# SkyKontrol-Display.net
KiCad netlist of a schematic drawn in EAGLE
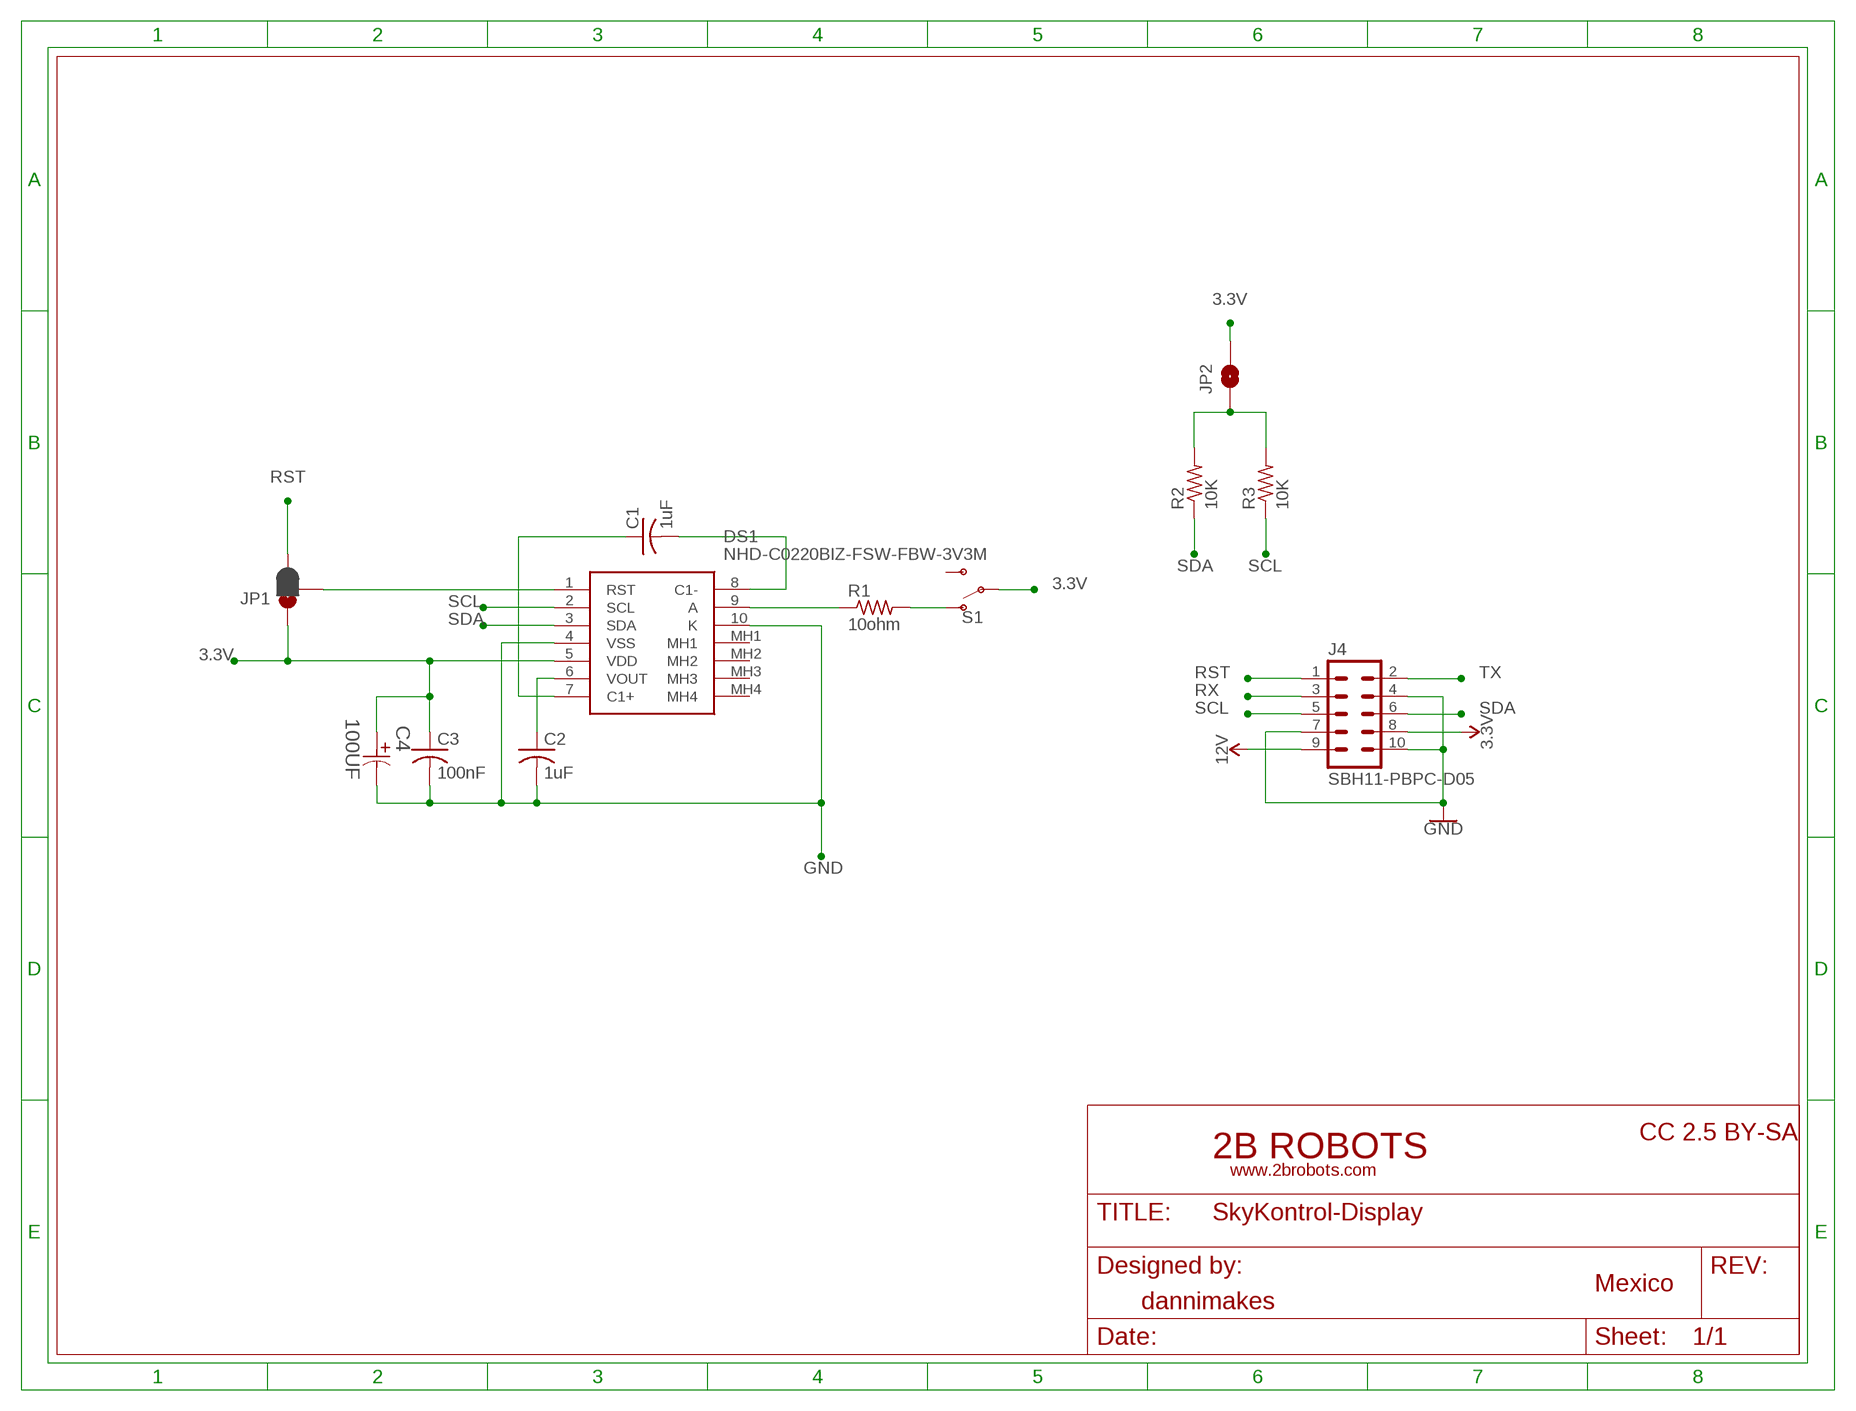
[diagram p0: schematic, sheet 1]

(export (version "E")
  (design (tool "Eeschema 10.0.6"))
  (components
    (comp (ref "C1")
      (value "1uF")
      (footprint "eagle-import:C0603K")
      (libsource (lib "eagle-import") (part "C-USC0603K"))
    )
    (comp (ref "C2")
      (value "1uF")
      (footprint "eagle-import:C0603K")
      (libsource (lib "eagle-import") (part "C-USC0603K"))
    )
    (comp (ref "C3")
      (value "100nF")
      (footprint "eagle-import:C0603K")
      (libsource (lib "eagle-import") (part "C-USC0603K"))
    )
    (comp (ref "C4")
      (value "100UF")
      (footprint "eagle-import:CAPAE660X800N")
      (fields (field (name "MPN") "EEE-HA1E101XP") (field (name "TOLERANCE") "±20 %"))
      (libsource (lib "eagle-import") (part "EEE--CASE-D8HA1E101XP"))
    )
    (comp (ref "DS1")
      (value "NHD-C0220BIZ-FSW-FBW-3V3M")
      (footprint "eagle-import:NHDC0220BIZFSWFBW3V3M")
      (fields (field (name "MOUSER_PART_NUMBER") "763-C0220BIZ-FSW-FBW"))
      (libsource (lib "eagle-import") (part "NHD-C0220BIZ-FSW-FBW-3V3M"))
    )
    (comp (ref "J4")
      (value "SBH11-PBPC-D05")
      (footprint "eagle-import:SBH11-PBPC-D05")
      (libsource (lib "eagle-import") (part "SBH11-PBPC-D05"))
    )
    (comp (ref "JP1")
      (value "JUMPER-SMT_3_1-NC_PASTE_SILK")
      (footprint "eagle-import:SMT-JUMPER_3_1-NC_PASTE_SILK")
      (libsource (lib "eagle-import") (part "JUMPER-SMT_3_1-NC_PASTE_SILK"))
    )
    (comp (ref "JP2")
      (value "JUMPER-SMT_2_NO_SILK")
      (footprint "eagle-import:SMT-JUMPER_2_NO_SILK")
      (libsource (lib "eagle-import") (part "JUMPER-SMT_2_NO_SILK"))
    )
    (comp (ref "R1")
      (value "10ohm")
      (footprint "eagle-import:R0805")
      (libsource (lib "eagle-import") (part "R-US_R0805"))
    )
    (comp (ref "R2")
      (value "10K")
      (footprint "eagle-import:R0805")
      (libsource (lib "eagle-import") (part "R-US_R0805"))
    )
    (comp (ref "R3")
      (value "10K")
      (footprint "eagle-import:R0805")
      (libsource (lib "eagle-import") (part "R-US_R0805"))
    )
    (comp (ref "S1")
      (value "SWITCH-SPDT-SMD-RIGHT-ANGLE")
      (footprint "eagle-import:SWITCH_SPST_SMD_A")
      (libsource (lib "eagle-import") (part "SWITCH-SPDT-SMD-RIGHT-ANGLE"))
    )
  )
  (nets
    (net (code "1") (name "/RST") (class "Default")
      (node (ref "J4") (pin "1") (pinfunction "1_1") (pintype "passive"))
      (node (ref "JP1") (pin "3") (pinfunction "3_3") (pintype "passive"))
    )
    (net (code "2") (name "/RX") (class "Default")
      (node (ref "J4") (pin "3") (pinfunction "3_3") (pintype "passive"))
    )
    (net (code "3") (name "/SCL") (class "Default")
      (node (ref "DS1") (pin "2") (pinfunction "SCL_2") (pintype "bidirectional"))
      (node (ref "J4") (pin "5") (pinfunction "5_5") (pintype "passive"))
      (node (ref "R3") (pin "1") (pinfunction "1_1") (pintype "passive"))
    )
    (net (code "4") (name "/SDA") (class "Default")
      (node (ref "DS1") (pin "3") (pinfunction "SDA_3") (pintype "bidirectional"))
      (node (ref "J4") (pin "6") (pinfunction "6_6") (pintype "passive"))
      (node (ref "R2") (pin "1") (pinfunction "1_1") (pintype "passive"))
    )
    (net (code "5") (name "/TX") (class "Default")
      (node (ref "J4") (pin "2") (pinfunction "2_2") (pintype "passive"))
    )
    (net (code "6") (name "3.3V") (class "Default")
      (node (ref "C3") (pin "1") (pinfunction "1_1") (pintype "passive"))
      (node (ref "C4") (pin "1") (pinfunction "1_1") (pintype "passive"))
      (node (ref "DS1") (pin "5") (pinfunction "VDD_5") (pintype "bidirectional"))
      (node (ref "J4") (pin "8") (pinfunction "8_8") (pintype "passive"))
      (node (ref "JP1") (pin "1") (pinfunction "1_1") (pintype "passive"))
      (node (ref "JP2") (pin "2") (pinfunction "2_2") (pintype "passive"))
      (node (ref "S1") (pin "2") (pinfunction "P_2") (pintype "passive"))
    )
    (net (code "7") (name "12V") (class "Default")
      (node (ref "J4") (pin "9") (pinfunction "9_9") (pintype "passive"))
    )
    (net (code "8") (name "GND") (class "Default")
      (node (ref "C2") (pin "2") (pinfunction "2_2") (pintype "passive"))
      (node (ref "C3") (pin "2") (pinfunction "2_2") (pintype "passive"))
      (node (ref "C4") (pin "2") (pinfunction "2_2") (pintype "passive"))
      (node (ref "DS1") (pin "10") (pinfunction "K_10") (pintype "bidirectional"))
      (node (ref "DS1") (pin "4") (pinfunction "VSS_4") (pintype "bidirectional"))
      (node (ref "J4") (pin "10") (pinfunction "10_10") (pintype "passive"))
      (node (ref "J4") (pin "4") (pinfunction "4_4") (pintype "passive"))
      (node (ref "J4") (pin "7") (pinfunction "7_7") (pintype "passive"))
    )
    (net (code "9") (name "Net-(DS1-A)") (class "Default")
      (node (ref "DS1") (pin "9") (pinfunction "A_9") (pintype "bidirectional"))
      (node (ref "R1") (pin "1") (pinfunction "1_1") (pintype "passive"))
    )
    (net (code "10") (name "Net-(DS1-C1+)") (class "Default")
      (node (ref "C1") (pin "1") (pinfunction "1_1") (pintype "passive"))
      (node (ref "DS1") (pin "7") (pinfunction "C1+_7") (pintype "bidirectional"))
    )
    (net (code "11") (name "Net-(DS1-C1-)") (class "Default")
      (node (ref "C1") (pin "2") (pinfunction "2_2") (pintype "passive"))
      (node (ref "DS1") (pin "8") (pinfunction "C1-_8") (pintype "bidirectional"))
    )
    (net (code "12") (name "Net-(DS1-RST)") (class "Default")
      (node (ref "DS1") (pin "1") (pinfunction "RST_1") (pintype "bidirectional"))
      (node (ref "JP1") (pin "2") (pinfunction "2_2") (pintype "passive"))
    )
    (net (code "13") (name "Net-(DS1-VOUT)") (class "Default")
      (node (ref "C2") (pin "1") (pinfunction "1_1") (pintype "passive"))
      (node (ref "DS1") (pin "6") (pinfunction "VOUT_6") (pintype "bidirectional"))
    )
    (net (code "14") (name "Net-(JP2-Pad1)") (class "Default")
      (node (ref "JP2") (pin "1") (pinfunction "1_1") (pintype "passive"))
      (node (ref "R2") (pin "2") (pinfunction "2_2") (pintype "passive"))
      (node (ref "R3") (pin "2") (pinfunction "2_2") (pintype "passive"))
    )
    (net (code "15") (name "Net-(S1-O)") (class "Default")
      (node (ref "R1") (pin "2") (pinfunction "2_2") (pintype "passive"))
      (node (ref "S1") (pin "1") (pinfunction "O_1") (pintype "passive"))
    )
    (net (code "16") (name "unconnected-(DS1-PadMH1)") (class "Default")
      (node (ref "DS1") (pin "MH1") (pinfunction "MH1_MH1") (pintype "bidirectional"))
    )
    (net (code "17") (name "unconnected-(DS1-PadMH2)") (class "Default")
      (node (ref "DS1") (pin "MH2") (pinfunction "MH2_MH2") (pintype "bidirectional"))
    )
    (net (code "18") (name "unconnected-(DS1-PadMH3)") (class "Default")
      (node (ref "DS1") (pin "MH3") (pinfunction "MH3_MH3") (pintype "bidirectional"))
    )
    (net (code "19") (name "unconnected-(DS1-PadMH4)") (class "Default")
      (node (ref "DS1") (pin "MH4") (pinfunction "MH4_MH4") (pintype "bidirectional"))
    )
    (net (code "20") (name "unconnected-(S1-S-Pad3)") (class "Default")
      (node (ref "S1") (pin "3") (pinfunction "S_3") (pintype "passive"))
    )
  )
)
